# top.net
KiCad netlist of a schematic drawn in Altium Designer
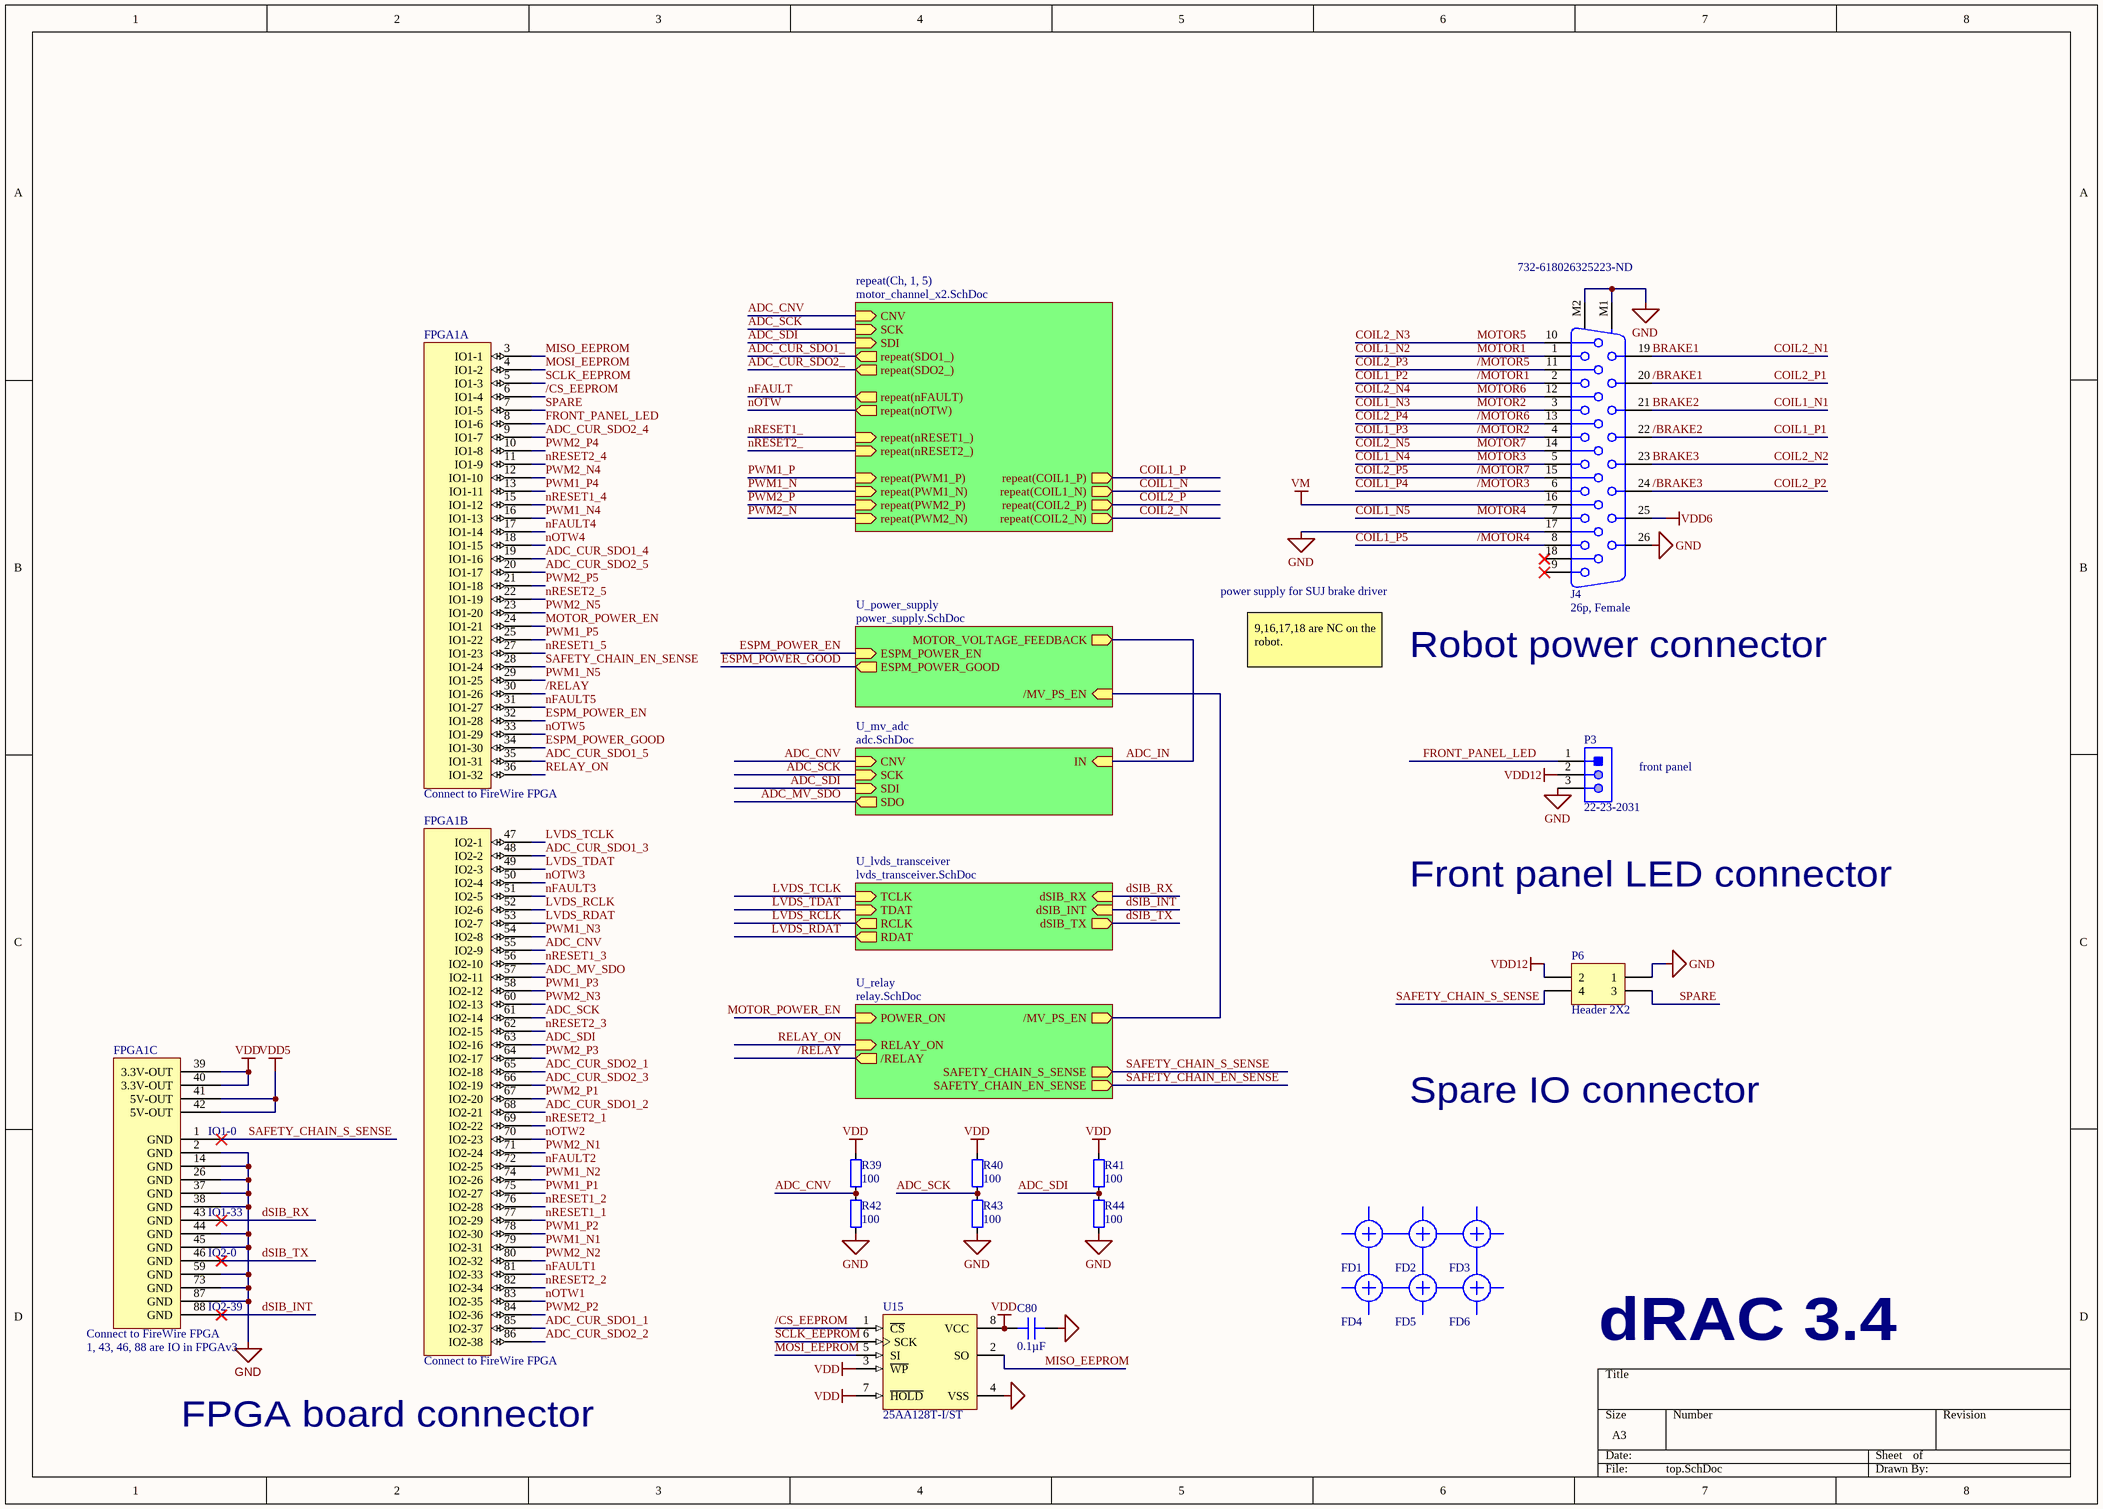
[diagram p0: top.SchDoc]

(export (version "E")
  (design (tool "Eeschema 10.0.6"))
  (components
    (comp (ref "C80")
      (value "0.1µF")
      (footprint "FP-GRM155-0_05-IPC_B")
      (description "CAP CER 0.1UF 25V X7R 0402")
      (fields (field (name "PART NUMBER") "04023C104KAT2A") (field (name "MANUFACTURER") "AVX Corporation"))
      (libsource (lib "Celestial Altium Library - altium_library") (part "Capacitor"))
    )
    (comp (ref "FD1") (value "FD") (footprint "FD") (libsource (lib "FPGA") (part "FD")))
    (comp (ref "FD2") (value "FD") (footprint "FD") (libsource (lib "FPGA") (part "FD")))
    (comp (ref "FD3") (value "FD") (footprint "FD") (libsource (lib "FPGA") (part "FD")))
    (comp (ref "FD4") (value "FD") (footprint "FD") (libsource (lib "FPGA") (part "FD")))
    (comp (ref "FD5") (value "FD") (footprint "FD") (libsource (lib "FPGA") (part "FD")))
    (comp (ref "FD6") (value "FD") (footprint "FD") (libsource (lib "FPGA") (part "FD")))
    (comp (ref "FPGA1")
      (value "Connect to FireWire FPGA")
      (footprint "drac_v3:FPGA-dummy")
      (libsource (lib "dvrk-s-pwm") (part "fpga_dummy"))
    )
    (comp (ref "J4")
      (value "26p, Female")
      (footprint "618026325223")
      (description "WR-DSUB Female High Density Angled PCB Connector without Hex Screw, 26p")
      (fields
        (field (name "PARTNUMBER") "618026325223")
        (field (name "SUPPLIER PART NUMBER 1") "732-618026325223-ND")
        (field (name "MANUFACTURER") "Wurth Electronics")
        (field (name "PUBLISHER") "Wurth Elektronik")
      )
      (libsource (lib "dvrk-s-pwm") (part "618026325223"))
    )
    (comp (ref "P3")
      (value "22-23-2031")
      (footprint "MOLX-22-23-2031_V")
      (description "Male Header, Pitch 2.54 mm, 1 x 3 Position, Height 8.18 mm, Tail Length 3.56 mm, RoHS, Bulk")
      (fields (field (name "MANUFACTURER") "Molex"))
      (libsource (lib "Altium Content Vault") (part "CN-1P-M-R3"))
    )
    (comp (ref "P6")
      (value "Header 2X2")
      (footprint "DF11-4DP-2DSA")
      (description "Header, 2-Pin, Dual row")
      (fields (field (name "PUBLISHER") "Altium Limited"))
      (libsource (lib "Miscellaneous Connectors") (part "Header 2X2"))
    )
    (comp (ref "R39")
      (value "100")
      (footprint "FP-CRCW0805-HPe3-IPC_B")
      (description "Resistor")
      (fields (field (name "Comment") "Res_0805"))
      (libsource (lib "SCH_Passive") (part "Res_0805"))
    )
    (comp (ref "R40")
      (value "100")
      (footprint "FP-CRCW0805-HPe3-IPC_B")
      (description "Resistor")
      (fields (field (name "Comment") "Res_0805"))
      (libsource (lib "SCH_Passive") (part "Res_0805"))
    )
    (comp (ref "R41")
      (value "100")
      (footprint "FP-CRCW0805-HPe3-IPC_B")
      (description "Resistor")
      (fields (field (name "Comment") "Res_0805"))
      (libsource (lib "SCH_Passive") (part "Res_0805"))
    )
    (comp (ref "R42")
      (value "100")
      (footprint "FP-CRCW0805-HPe3-IPC_B")
      (description "Resistor")
      (fields (field (name "Comment") "Res_0805"))
      (libsource (lib "SCH_Passive") (part "Res_0805"))
    )
    (comp (ref "R43")
      (value "100")
      (footprint "FP-CRCW0805-HPe3-IPC_B")
      (description "Resistor")
      (fields (field (name "Comment") "Res_0805"))
      (libsource (lib "SCH_Passive") (part "Res_0805"))
    )
    (comp (ref "R44")
      (value "100")
      (footprint "FP-CRCW0805-HPe3-IPC_B")
      (description "Resistor")
      (fields (field (name "Comment") "Res_0805"))
      (libsource (lib "SCH_Passive") (part "Res_0805"))
    )
    (comp (ref "U15")
      (value "25AA128T-I/ST")
      (footprint "TSSOP-ST8_N")
      (description "128K SPI Bus Serial EEPROM, 8-Pin TSSOP, Industrial Temperature, Tape and Reel")
      (libsource (lib "Altium Content Vault") (part "MEM-SEEPROM-25AA1024-8"))
    )
  )
  (nets
    (net (code "1") (name "/ADC_CNV") (class "Default")
      (node (ref "FPGA1") (pin "55") (pinfunction "IO2-9_55") (pintype "bidirectional"))
      (node (ref "R39") (pin "1") (pinfunction "1_1") (pintype "passive"))
      (node (ref "R42") (pin "2") (pinfunction "2_2") (pintype "passive"))
    )
    (net (code "3") (name "/ADC_CUR_SDO1_1") (class "Default")
      (node (ref "FPGA1") (pin "85") (pinfunction "IO2-37_85") (pintype "bidirectional"))
    )
    (net (code "4") (name "/ADC_CUR_SDO1_2") (class "Default")
      (node (ref "FPGA1") (pin "68") (pinfunction "IO2-21_68") (pintype "bidirectional"))
    )
    (net (code "5") (name "/ADC_CUR_SDO1_3") (class "Default")
      (node (ref "FPGA1") (pin "48") (pinfunction "IO2-2_48") (pintype "bidirectional"))
    )
    (net (code "6") (name "/ADC_CUR_SDO1_4") (class "Default")
      (node (ref "FPGA1") (pin "19") (pinfunction "IO1-16_19") (pintype "bidirectional"))
    )
    (net (code "7") (name "/ADC_CUR_SDO1_5") (class "Default")
      (node (ref "FPGA1") (pin "35") (pinfunction "IO1-31_35") (pintype "bidirectional"))
    )
    (net (code "9") (name "/ADC_CUR_SDO2_1") (class "Default")
      (node (ref "FPGA1") (pin "65") (pinfunction "IO2-18_65") (pintype "bidirectional"))
    )
    (net (code "10") (name "/ADC_CUR_SDO2_2") (class "Default")
      (node (ref "FPGA1") (pin "86") (pinfunction "IO2-38_86") (pintype "bidirectional"))
    )
    (net (code "11") (name "/ADC_CUR_SDO2_3") (class "Default")
      (node (ref "FPGA1") (pin "66") (pinfunction "IO2-19_66") (pintype "bidirectional"))
    )
    (net (code "12") (name "/ADC_CUR_SDO2_4") (class "Default")
      (node (ref "FPGA1") (pin "9") (pinfunction "IO1-7_9") (pintype "bidirectional"))
    )
    (net (code "13") (name "/ADC_CUR_SDO2_5") (class "Default")
      (node (ref "FPGA1") (pin "20") (pinfunction "IO1-17_20") (pintype "bidirectional"))
    )
    (net (code "15") (name "/ADC_MV_SDO") (class "Default")
      (node (ref "FPGA1") (pin "57") (pinfunction "IO2-11_57") (pintype "bidirectional"))
    )
    (net (code "16") (name "/ADC_SCK") (class "Default")
      (node (ref "FPGA1") (pin "61") (pinfunction "IO2-14_61") (pintype "bidirectional"))
      (node (ref "R40") (pin "1") (pinfunction "1_1") (pintype "passive"))
      (node (ref "R43") (pin "2") (pinfunction "2_2") (pintype "passive"))
    )
    (net (code "17") (name "/ADC_SDI") (class "Default")
      (node (ref "FPGA1") (pin "63") (pinfunction "IO2-16_63") (pintype "bidirectional"))
      (node (ref "R41") (pin "1") (pinfunction "1_1") (pintype "passive"))
      (node (ref "R44") (pin "2") (pinfunction "2_2") (pintype "passive"))
    )
    (net (code "18") (name "/BRAKE1") (class "Default")
      (node (ref "J4") (pin "19") (pinfunction "19_19") (pintype "passive"))
    )
    (net (code "19") (name "/BRAKE2") (class "Default")
      (node (ref "J4") (pin "21") (pinfunction "21_21") (pintype "passive"))
    )
    (net (code "20") (name "/BRAKE3") (class "Default")
      (node (ref "J4") (pin "23") (pinfunction "23_23") (pintype "passive"))
    )
    (net (code "22") (name "/COIL1_N2") (class "Default")
      (node (ref "J4") (pin "1") (pinfunction "1_1") (pintype "passive"))
    )
    (net (code "23") (name "/COIL1_N3") (class "Default")
      (node (ref "J4") (pin "3") (pinfunction "3_3") (pintype "passive"))
    )
    (net (code "24") (name "/COIL1_N4") (class "Default")
      (node (ref "J4") (pin "5") (pinfunction "5_5") (pintype "passive"))
    )
    (net (code "25") (name "/COIL1_N5") (class "Default")
      (node (ref "J4") (pin "7") (pinfunction "7_7") (pintype "passive"))
    )
    (net (code "27") (name "/COIL1_P1") (class "Default")
      (node (ref "J4") (pin "22") (pinfunction "22_22") (pintype "passive"))
    )
    (net (code "28") (name "/COIL1_P2") (class "Default")
      (node (ref "J4") (pin "2") (pinfunction "2_2") (pintype "passive"))
    )
    (net (code "29") (name "/COIL1_P3") (class "Default")
      (node (ref "J4") (pin "4") (pinfunction "4_4") (pintype "passive"))
    )
    (net (code "30") (name "/COIL1_P4") (class "Default")
      (node (ref "J4") (pin "6") (pinfunction "6_6") (pintype "passive"))
    )
    (net (code "31") (name "/COIL1_P5") (class "Default")
      (node (ref "J4") (pin "8") (pinfunction "8_8") (pintype "passive"))
    )
    (net (code "33") (name "/COIL2_N3") (class "Default")
      (node (ref "J4") (pin "10") (pinfunction "10_10") (pintype "passive"))
    )
    (net (code "34") (name "/COIL2_N4") (class "Default")
      (node (ref "J4") (pin "12") (pinfunction "12_12") (pintype "passive"))
    )
    (net (code "35") (name "/COIL2_N5") (class "Default")
      (node (ref "J4") (pin "14") (pinfunction "14_14") (pintype "passive"))
    )
    (net (code "37") (name "/COIL2_P1") (class "Default")
      (node (ref "J4") (pin "20") (pinfunction "20_20") (pintype "passive"))
    )
    (net (code "38") (name "/COIL2_P2") (class "Default")
      (node (ref "J4") (pin "24") (pinfunction "24_24") (pintype "passive"))
    )
    (net (code "39") (name "/COIL2_P3") (class "Default")
      (node (ref "J4") (pin "11") (pinfunction "11_11") (pintype "passive"))
    )
    (net (code "40") (name "/COIL2_P4") (class "Default")
      (node (ref "J4") (pin "13") (pinfunction "13_13") (pintype "passive"))
    )
    (net (code "41") (name "/COIL2_P5") (class "Default")
      (node (ref "J4") (pin "15") (pinfunction "15_15") (pintype "passive"))
    )
    (net (code "42") (name "/ESPM_POWER_EN") (class "Default")
      (node (ref "FPGA1") (pin "32") (pinfunction "IO1-28_32") (pintype "bidirectional"))
    )
    (net (code "43") (name "/ESPM_POWER_GOOD") (class "Default")
      (node (ref "FPGA1") (pin "34") (pinfunction "IO1-30_34") (pintype "bidirectional"))
    )
    (net (code "44") (name "/FRONT_PANEL_LED") (class "Default")
      (node (ref "FPGA1") (pin "8") (pinfunction "IO1-6_8") (pintype "bidirectional"))
      (node (ref "P3") (pin "1") (pinfunction "1_1") (pintype "passive"))
    )
    (net (code "45") (name "/LVDS_RCLK") (class "Default")
      (node (ref "FPGA1") (pin "52") (pinfunction "IO2-6_52") (pintype "bidirectional"))
    )
    (net (code "46") (name "/LVDS_RDAT") (class "Default")
      (node (ref "FPGA1") (pin "53") (pinfunction "IO2-7_53") (pintype "bidirectional"))
    )
    (net (code "47") (name "/LVDS_TCLK") (class "Default")
      (node (ref "FPGA1") (pin "47") (pinfunction "IO2-1_47") (pintype "bidirectional"))
    )
    (net (code "48") (name "/LVDS_TDAT") (class "Default")
      (node (ref "FPGA1") (pin "49") (pinfunction "IO2-3_49") (pintype "bidirectional"))
    )
    (net (code "49") (name "/MISO_EEPROM") (class "Default")
      (node (ref "FPGA1") (pin "3") (pinfunction "IO1-1_3") (pintype "bidirectional"))
      (node (ref "U15") (pin "2") (pinfunction "SO_2") (pintype "tri_state"))
    )
    (net (code "50") (name "/MOSI_EEPROM") (class "Default")
      (node (ref "FPGA1") (pin "4") (pinfunction "IO1-2_4") (pintype "bidirectional"))
      (node (ref "U15") (pin "5") (pinfunction "SI_5") (pintype "input"))
    )
    (net (code "51") (name "/MOTOR_POWER_EN") (class "Default")
      (node (ref "FPGA1") (pin "24") (pinfunction "IO1-21_24") (pintype "bidirectional"))
    )
    (net (code "53") (name "/PWM1_N1") (class "Default")
      (node (ref "FPGA1") (pin "79") (pinfunction "IO2-31_79") (pintype "bidirectional"))
    )
    (net (code "54") (name "/PWM1_N2") (class "Default")
      (node (ref "FPGA1") (pin "74") (pinfunction "IO2-26_74") (pintype "bidirectional"))
    )
    (net (code "55") (name "/PWM1_N3") (class "Default")
      (node (ref "FPGA1") (pin "54") (pinfunction "IO2-8_54") (pintype "bidirectional"))
    )
    (net (code "56") (name "/PWM1_N4") (class "Default")
      (node (ref "FPGA1") (pin "16") (pinfunction "IO1-13_16") (pintype "bidirectional"))
    )
    (net (code "57") (name "/PWM1_N5") (class "Default")
      (node (ref "FPGA1") (pin "29") (pinfunction "IO1-25_29") (pintype "bidirectional"))
    )
    (net (code "59") (name "/PWM1_P1") (class "Default")
      (node (ref "FPGA1") (pin "75") (pinfunction "IO2-27_75") (pintype "bidirectional"))
    )
    (net (code "60") (name "/PWM1_P2") (class "Default")
      (node (ref "FPGA1") (pin "78") (pinfunction "IO2-30_78") (pintype "bidirectional"))
    )
    (net (code "61") (name "/PWM1_P3") (class "Default")
      (node (ref "FPGA1") (pin "58") (pinfunction "IO2-12_58") (pintype "bidirectional"))
    )
    (net (code "62") (name "/PWM1_P4") (class "Default")
      (node (ref "FPGA1") (pin "13") (pinfunction "IO1-11_13") (pintype "bidirectional"))
    )
    (net (code "63") (name "/PWM1_P5") (class "Default")
      (node (ref "FPGA1") (pin "25") (pinfunction "IO1-22_25") (pintype "bidirectional"))
    )
    (net (code "65") (name "/PWM2_N1") (class "Default")
      (node (ref "FPGA1") (pin "71") (pinfunction "IO2-24_71") (pintype "bidirectional"))
    )
    (net (code "66") (name "/PWM2_N2") (class "Default")
      (node (ref "FPGA1") (pin "80") (pinfunction "IO2-32_80") (pintype "bidirectional"))
    )
    (net (code "67") (name "/PWM2_N3") (class "Default")
      (node (ref "FPGA1") (pin "60") (pinfunction "IO2-13_60") (pintype "bidirectional"))
    )
    (net (code "68") (name "/PWM2_N4") (class "Default")
      (node (ref "FPGA1") (pin "12") (pinfunction "IO1-10_12") (pintype "bidirectional"))
    )
    (net (code "69") (name "/PWM2_N5") (class "Default")
      (node (ref "FPGA1") (pin "23") (pinfunction "IO1-20_23") (pintype "bidirectional"))
    )
    (net (code "71") (name "/PWM2_P1") (class "Default")
      (node (ref "FPGA1") (pin "67") (pinfunction "IO2-20_67") (pintype "bidirectional"))
    )
    (net (code "72") (name "/PWM2_P2") (class "Default")
      (node (ref "FPGA1") (pin "84") (pinfunction "IO2-36_84") (pintype "bidirectional"))
    )
    (net (code "73") (name "/PWM2_P3") (class "Default")
      (node (ref "FPGA1") (pin "64") (pinfunction "IO2-17_64") (pintype "bidirectional"))
    )
    (net (code "74") (name "/PWM2_P4") (class "Default")
      (node (ref "FPGA1") (pin "10") (pinfunction "IO1-8_10") (pintype "bidirectional"))
    )
    (net (code "75") (name "/PWM2_P5") (class "Default")
      (node (ref "FPGA1") (pin "21") (pinfunction "IO1-18_21") (pintype "bidirectional"))
    )
    (net (code "76") (name "/RELAY_ON") (class "Default")
      (node (ref "FPGA1") (pin "36") (pinfunction "IO1-32_36") (pintype "bidirectional"))
    )
    (net (code "77") (name "/SAFETY_CHAIN_EN_SENSE") (class "Default")
      (node (ref "FPGA1") (pin "28") (pinfunction "IO1-24_28") (pintype "bidirectional"))
    )
    (net (code "78") (name "/SAFETY_CHAIN_S_SENSE") (class "Default")
      (node (ref "FPGA1") (pin "1") (pinfunction "GND_1") (pintype "power_in"))
      (node (ref "P6") (pin "4") (pinfunction "4_4") (pintype "passive"))
    )
    (net (code "79") (name "/SCLK_EEPROM") (class "Default")
      (node (ref "FPGA1") (pin "5") (pinfunction "IO1-3_5") (pintype "bidirectional"))
      (node (ref "U15") (pin "6") (pinfunction "SCK_6") (pintype "input"))
    )
    (net (code "80") (name "/SPARE") (class "Default")
      (node (ref "FPGA1") (pin "7") (pinfunction "IO1-5_7") (pintype "bidirectional"))
      (node (ref "P6") (pin "3") (pinfunction "3_3") (pintype "passive"))
    )
    (net (code "81") (name "/dSIB_INT") (class "Default")
      (node (ref "FPGA1") (pin "88") (pinfunction "GND_88") (pintype "power_in"))
    )
    (net (code "82") (name "/dSIB_RX") (class "Default")
      (node (ref "FPGA1") (pin "43") (pinfunction "GND_43") (pintype "power_in"))
    )
    (net (code "83") (name "/dSIB_TX") (class "Default")
      (node (ref "FPGA1") (pin "46") (pinfunction "GND_46") (pintype "power_in"))
    )
    (net (code "85") (name "/nFAULT1") (class "Default")
      (node (ref "FPGA1") (pin "81") (pinfunction "IO2-33_81") (pintype "bidirectional"))
    )
    (net (code "86") (name "/nFAULT2") (class "Default")
      (node (ref "FPGA1") (pin "72") (pinfunction "IO2-25_72") (pintype "bidirectional"))
    )
    (net (code "87") (name "/nFAULT3") (class "Default")
      (node (ref "FPGA1") (pin "51") (pinfunction "IO2-5_51") (pintype "bidirectional"))
    )
    (net (code "88") (name "/nFAULT4") (class "Default")
      (node (ref "FPGA1") (pin "17") (pinfunction "IO1-14_17") (pintype "bidirectional"))
    )
    (net (code "89") (name "/nFAULT5") (class "Default")
      (node (ref "FPGA1") (pin "31") (pinfunction "IO1-27_31") (pintype "bidirectional"))
    )
    (net (code "91") (name "/nOTW1") (class "Default")
      (node (ref "FPGA1") (pin "83") (pinfunction "IO2-35_83") (pintype "bidirectional"))
    )
    (net (code "92") (name "/nOTW2") (class "Default")
      (node (ref "FPGA1") (pin "70") (pinfunction "IO2-23_70") (pintype "bidirectional"))
    )
    (net (code "93") (name "/nOTW3") (class "Default")
      (node (ref "FPGA1") (pin "50") (pinfunction "IO2-4_50") (pintype "bidirectional"))
    )
    (net (code "94") (name "/nOTW4") (class "Default")
      (node (ref "FPGA1") (pin "18") (pinfunction "IO1-15_18") (pintype "bidirectional"))
    )
    (net (code "95") (name "/nOTW5") (class "Default")
      (node (ref "FPGA1") (pin "33") (pinfunction "IO1-29_33") (pintype "bidirectional"))
    )
    (net (code "97") (name "/nRESET1_1") (class "Default")
      (node (ref "FPGA1") (pin "77") (pinfunction "IO2-29_77") (pintype "bidirectional"))
    )
    (net (code "98") (name "/nRESET1_2") (class "Default")
      (node (ref "FPGA1") (pin "76") (pinfunction "IO2-28_76") (pintype "bidirectional"))
    )
    (net (code "99") (name "/nRESET1_3") (class "Default")
      (node (ref "FPGA1") (pin "56") (pinfunction "IO2-10_56") (pintype "bidirectional"))
    )
    (net (code "100") (name "/nRESET1_4") (class "Default")
      (node (ref "FPGA1") (pin "15") (pinfunction "IO1-12_15") (pintype "bidirectional"))
    )
    (net (code "101") (name "/nRESET1_5") (class "Default")
      (node (ref "FPGA1") (pin "27") (pinfunction "IO1-23_27") (pintype "bidirectional"))
    )
    (net (code "103") (name "/nRESET2_1") (class "Default")
      (node (ref "FPGA1") (pin "69") (pinfunction "IO2-22_69") (pintype "bidirectional"))
    )
    (net (code "104") (name "/nRESET2_2") (class "Default")
      (node (ref "FPGA1") (pin "82") (pinfunction "IO2-34_82") (pintype "bidirectional"))
    )
    (net (code "105") (name "/nRESET2_3") (class "Default")
      (node (ref "FPGA1") (pin "62") (pinfunction "IO2-15_62") (pintype "bidirectional"))
    )
    (net (code "106") (name "/nRESET2_4") (class "Default")
      (node (ref "FPGA1") (pin "11") (pinfunction "IO1-9_11") (pintype "bidirectional"))
    )
    (net (code "107") (name "/nRESET2_5") (class "Default")
      (node (ref "FPGA1") (pin "22") (pinfunction "IO1-19_22") (pintype "bidirectional"))
    )
    (net (code "108") (name "/{slash}CS_EEPROM") (class "Default")
      (node (ref "FPGA1") (pin "6") (pinfunction "IO1-4_6") (pintype "bidirectional"))
      (node (ref "U15") (pin "1") (pinfunction "~{CS}_1") (pintype "input"))
    )
    (net (code "110") (name "/{slash}RELAY") (class "Default")
      (node (ref "FPGA1") (pin "30") (pinfunction "IO1-26_30") (pintype "bidirectional"))
    )
    (net (code "111") (name "GND") (class "Default")
      (node (ref "C80") (pin "2") (pinfunction "2_2") (pintype "passive"))
      (node (ref "FPGA1") (pin "14") (pinfunction "GND_14") (pintype "power_in"))
      (node (ref "FPGA1") (pin "2") (pinfunction "GND_2") (pintype "power_in"))
      (node (ref "FPGA1") (pin "26") (pinfunction "GND_26") (pintype "power_in"))
      (node (ref "FPGA1") (pin "37") (pinfunction "GND_37") (pintype "power_in"))
      (node (ref "FPGA1") (pin "38") (pinfunction "GND_38") (pintype "power_in"))
      (node (ref "FPGA1") (pin "44") (pinfunction "GND_44") (pintype "power_in"))
      (node (ref "FPGA1") (pin "45") (pinfunction "GND_45") (pintype "power_in"))
      (node (ref "FPGA1") (pin "59") (pinfunction "GND_59") (pintype "power_in"))
      (node (ref "FPGA1") (pin "73") (pinfunction "GND_73") (pintype "power_in"))
      (node (ref "FPGA1") (pin "87") (pinfunction "GND_87") (pintype "power_in"))
      (node (ref "J4") (pin "17") (pinfunction "17_17") (pintype "passive"))
      (node (ref "J4") (pin "26") (pinfunction "26_26") (pintype "passive"))
      (node (ref "J4") (pin "M1") (pinfunction "M1_M1") (pintype "passive"))
      (node (ref "J4") (pin "M2") (pinfunction "M2_M2") (pintype "passive"))
      (node (ref "P3") (pin "3") (pinfunction "3_3") (pintype "passive"))
      (node (ref "P6") (pin "1") (pinfunction "1_1") (pintype "passive"))
      (node (ref "R42") (pin "1") (pinfunction "1_1") (pintype "passive"))
      (node (ref "R43") (pin "1") (pinfunction "1_1") (pintype "passive"))
      (node (ref "R44") (pin "1") (pinfunction "1_1") (pintype "passive"))
      (node (ref "U15") (pin "4") (pinfunction "VSS_4") (pintype "power_in"))
    )
    (net (code "112") (name "VDD") (class "Default")
      (node (ref "C80") (pin "1") (pinfunction "1_1") (pintype "passive"))
      (node (ref "FPGA1") (pin "39") (pinfunction "3.3V-OUT_39") (pintype "power_in"))
      (node (ref "FPGA1") (pin "40") (pinfunction "3.3V-OUT_40") (pintype "power_in"))
      (node (ref "R39") (pin "2") (pinfunction "2_2") (pintype "passive"))
      (node (ref "R40") (pin "2") (pinfunction "2_2") (pintype "passive"))
      (node (ref "R41") (pin "2") (pinfunction "2_2") (pintype "passive"))
      (node (ref "U15") (pin "3") (pinfunction "~{WP}_3") (pintype "input"))
      (node (ref "U15") (pin "7") (pinfunction "~{HOLD}_7") (pintype "input"))
      (node (ref "U15") (pin "8") (pinfunction "VCC_8") (pintype "power_in"))
    )
    (net (code "113") (name "VDD5") (class "Default")
      (node (ref "FPGA1") (pin "41") (pinfunction "5V-OUT_41") (pintype "power_in"))
      (node (ref "FPGA1") (pin "42") (pinfunction "5V-OUT_42") (pintype "power_in"))
    )
    (net (code "114") (name "VDD6") (class "Default")
      (node (ref "J4") (pin "25") (pinfunction "25_25") (pintype "passive"))
    )
    (net (code "115") (name "VDD12") (class "Default")
      (node (ref "P3") (pin "2") (pinfunction "2_2") (pintype "passive"))
      (node (ref "P6") (pin "2") (pinfunction "2_2") (pintype "passive"))
    )
    (net (code "116") (name "VM") (class "Default")
      (node (ref "J4") (pin "16") (pinfunction "16_16") (pintype "passive"))
    )
    (net (code "117") (name "unconnected-(J4-Pad9)") (class "Default")
      (node (ref "J4") (pin "9") (pinfunction "9_9") (pintype "passive+no_connect"))
    )
    (net (code "118") (name "unconnected-(J4-Pad18)") (class "Default")
      (node (ref "J4") (pin "18") (pinfunction "18_18") (pintype "passive+no_connect"))
    )
  )
)
